# Keg_Cop_-_RJ45_-_6-Pack_Tallboy.net
KiCad netlist of a schematic drawn in EAGLE
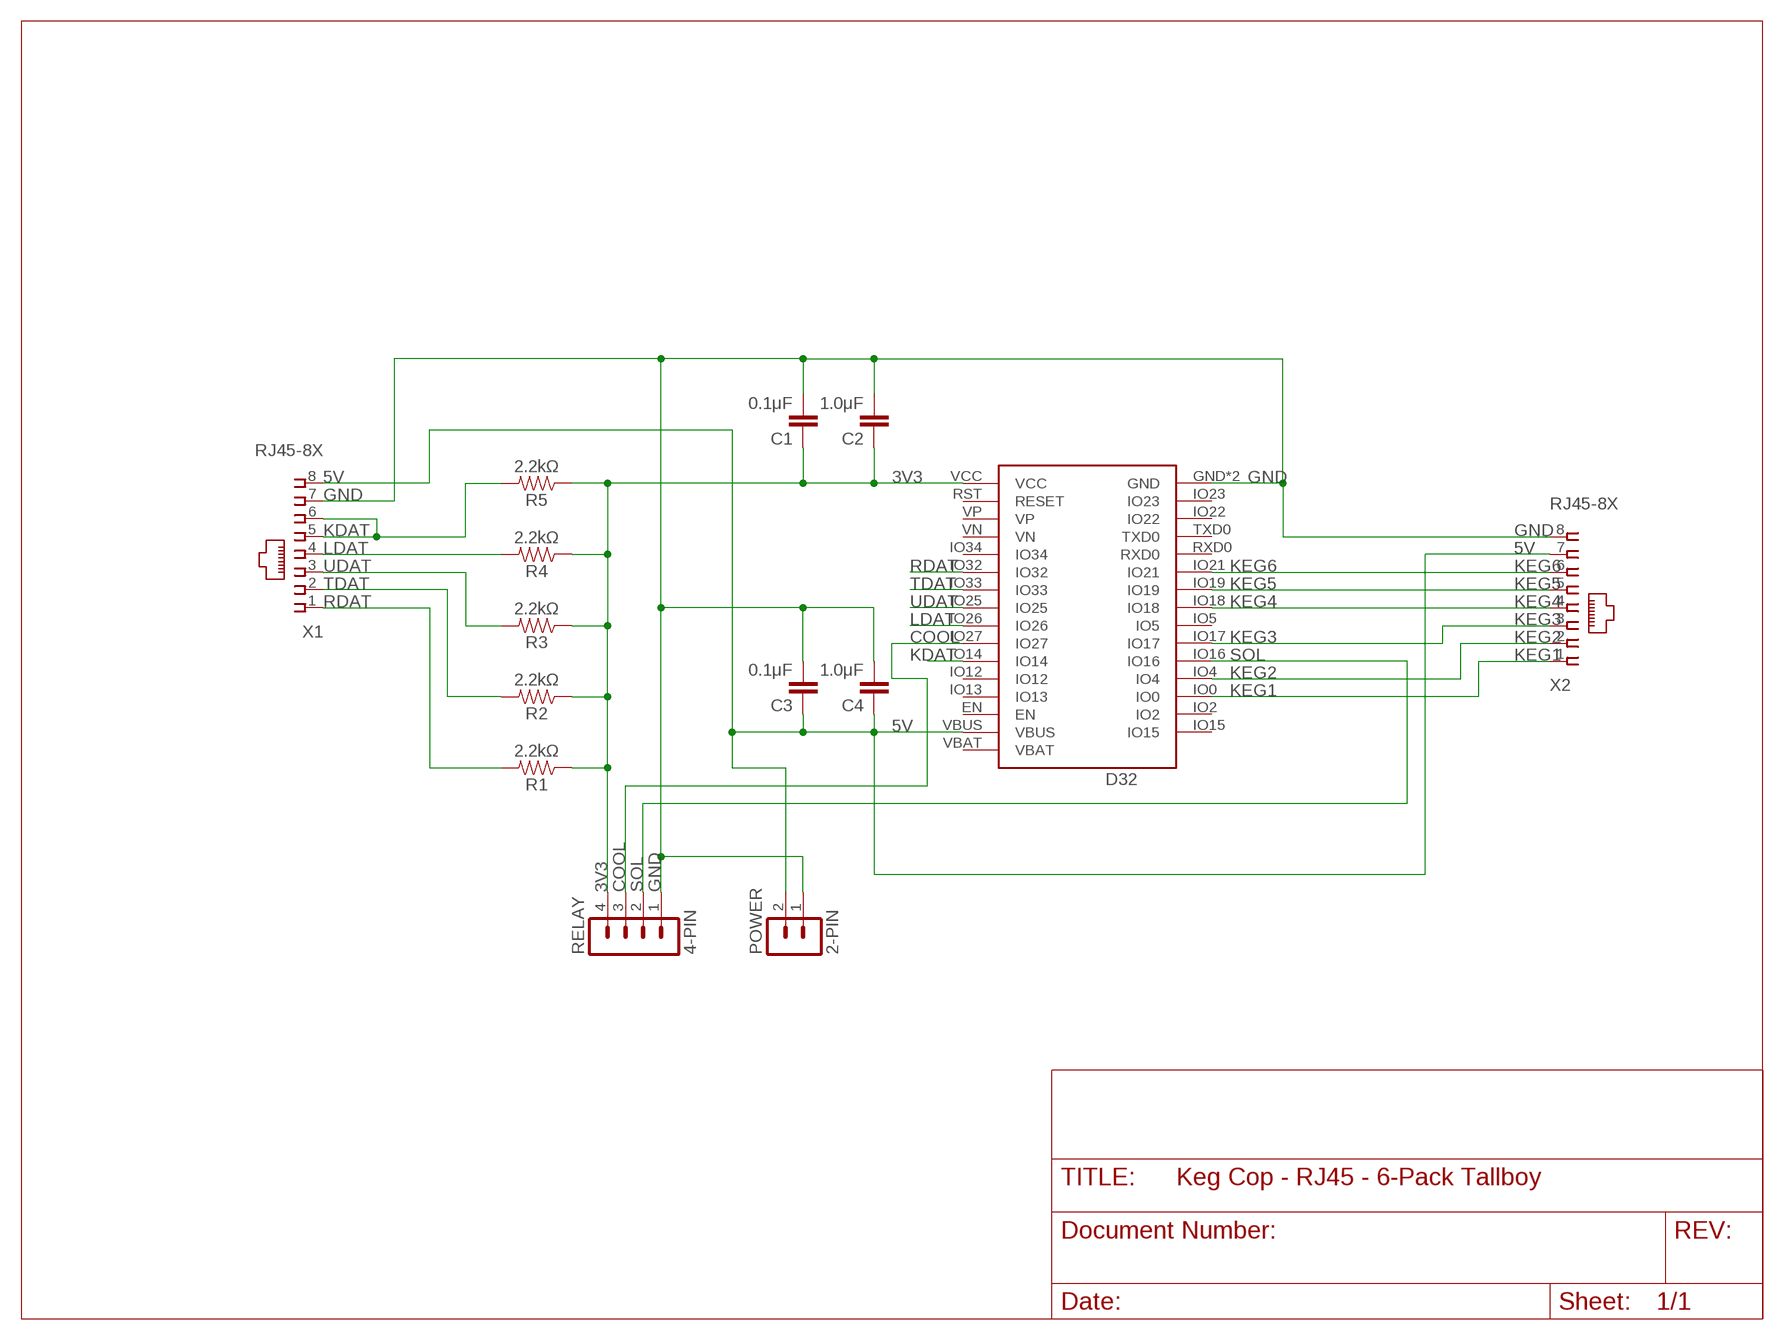
[diagram p0: schematic, sheet 1]

(export (version "E")
  (design (tool "Eeschema 10.0.6"))
  (components
    (comp (ref "C1")
      (value "0.1μF")
      (footprint "eagle-import:CAP_PTH-2.54")
      (libsource (lib "eagle-import") (part "CAP_CERAMIC_2.54"))
    )
    (comp (ref "C2")
      (value "1.0μF")
      (footprint "eagle-import:CAP_PTH-2.54")
      (libsource (lib "eagle-import") (part "CAP_CERAMIC_2.54"))
    )
    (comp (ref "C3")
      (value "0.1μF")
      (footprint "eagle-import:CAP_PTH-2.54")
      (libsource (lib "eagle-import") (part "CAP_CERAMIC_2.54"))
    )
    (comp (ref "C4")
      (value "1.0μF")
      (footprint "eagle-import:CAP_PTH-2.54")
      (libsource (lib "eagle-import") (part "CAP_CERAMIC_2.54"))
    )
    (comp (ref "D32")
      (value "Lolin D32")
      (footprint "eagle-import:D32_NO_BATT")
      (libsource (lib "eagle-import") (part "WEMOS-D32D32_NO_BATT"))
    )
    (comp (ref "POWER")
      (value "2-PIN")
      (footprint "eagle-import:HDR-2_VERT")
      (libsource (lib "eagle-import") (part "HDR-2"))
    )
    (comp (ref "R1")
      (value "2.2kΩ")
      (footprint "eagle-import:AXIAL-0.3")
      (libsource (lib "eagle-import") (part "RESISTORAXIAL-0.3"))
    )
    (comp (ref "R2")
      (value "2.2kΩ")
      (footprint "eagle-import:AXIAL-0.3")
      (libsource (lib "eagle-import") (part "RESISTORAXIAL-0.3"))
    )
    (comp (ref "R3")
      (value "2.2kΩ")
      (footprint "eagle-import:AXIAL-0.3")
      (libsource (lib "eagle-import") (part "RESISTORAXIAL-0.3"))
    )
    (comp (ref "R4")
      (value "2.2kΩ")
      (footprint "eagle-import:AXIAL-0.3")
      (libsource (lib "eagle-import") (part "RESISTORAXIAL-0.3"))
    )
    (comp (ref "R5")
      (value "2.2kΩ")
      (footprint "eagle-import:AXIAL-0.3")
      (libsource (lib "eagle-import") (part "RESISTORAXIAL-0.3"))
    )
    (comp (ref "RELAY")
      (value "4-PIN")
      (footprint "eagle-import:MA04-1")
      (libsource (lib "eagle-import") (part "MA04-1"))
    )
    (comp (ref "X1")
      (value "RJ45-8X")
      (footprint "eagle-import:RJ45-NO-SHIELD")
      (libsource (lib "eagle-import") (part "RJ45-8X"))
    )
    (comp (ref "X2")
      (value "RJ45-8X")
      (footprint "eagle-import:RJ45-NO-SHIELD")
      (libsource (lib "eagle-import") (part "RJ45-8X"))
    )
  )
  (nets
    (net (code "1") (name "/3V3") (class "Default")
      (node (ref "C1") (pin "1") (pinfunction "1_1") (pintype "passive"))
      (node (ref "C2") (pin "1") (pinfunction "1_1") (pintype "passive"))
      (node (ref "D32") (pin "VCC") (pinfunction "VCC_VCC") (pintype "power_in"))
      (node (ref "R1") (pin "P$1") (pinfunction "1_P$1") (pintype "passive"))
      (node (ref "R2") (pin "P$1") (pinfunction "1_P$1") (pintype "passive"))
      (node (ref "R3") (pin "P$1") (pinfunction "1_P$1") (pintype "passive"))
      (node (ref "R4") (pin "P$1") (pinfunction "1_P$1") (pintype "passive"))
      (node (ref "R5") (pin "P$1") (pinfunction "1_P$1") (pintype "passive"))
      (node (ref "RELAY") (pin "4") (pinfunction "4_4") (pintype "passive"))
    )
    (net (code "2") (name "/5V") (class "Default")
      (node (ref "C3") (pin "1") (pinfunction "1_1") (pintype "passive"))
      (node (ref "C4") (pin "1") (pinfunction "1_1") (pintype "passive"))
      (node (ref "D32") (pin "VBUS") (pinfunction "VBUS_VBUS") (pintype "bidirectional"))
      (node (ref "POWER") (pin "2") (pinfunction "2_2") (pintype "passive"))
      (node (ref "X1") (pin "8") (pinfunction "8_8") (pintype "passive"))
      (node (ref "X2") (pin "7") (pinfunction "7_7") (pintype "passive"))
    )
    (net (code "3") (name "/COOL") (class "Default")
      (node (ref "D32") (pin "IO27") (pinfunction "IO27_IO27") (pintype "bidirectional"))
      (node (ref "RELAY") (pin "3") (pinfunction "3_3") (pintype "passive"))
    )
    (net (code "4") (name "/GND") (class "Default")
      (node (ref "C1") (pin "2") (pinfunction "2_2") (pintype "passive"))
      (node (ref "C2") (pin "2") (pinfunction "2_2") (pintype "passive"))
      (node (ref "C3") (pin "2") (pinfunction "2_2") (pintype "passive"))
      (node (ref "C4") (pin "2") (pinfunction "2_2") (pintype "passive"))
      (node (ref "D32") (pin "GND") (pinfunction "GND_GND") (pintype "power_in"))
      (node (ref "D32") (pin "GND2") (pinfunction "GND_GND2") (pintype "power_in"))
      (node (ref "POWER") (pin "1") (pinfunction "1_1") (pintype "passive"))
      (node (ref "RELAY") (pin "1") (pinfunction "1_1") (pintype "passive"))
      (node (ref "X1") (pin "7") (pinfunction "7_7") (pintype "passive"))
      (node (ref "X2") (pin "8") (pinfunction "8_8") (pintype "passive"))
    )
    (net (code "5") (name "/KDAT") (class "Default")
      (node (ref "D32") (pin "IO14") (pinfunction "IO14_IO14") (pintype "bidirectional"))
      (node (ref "R5") (pin "P$2") (pinfunction "2_P$2") (pintype "passive"))
      (node (ref "X1") (pin "5") (pinfunction "5_5") (pintype "passive"))
      (node (ref "X1") (pin "6") (pinfunction "6_6") (pintype "passive"))
    )
    (net (code "6") (name "/KEG1") (class "Default")
      (node (ref "D32") (pin "IO0") (pinfunction "IO0_IO0") (pintype "bidirectional"))
      (node (ref "X2") (pin "1") (pinfunction "1_1") (pintype "passive"))
    )
    (net (code "7") (name "/KEG2") (class "Default")
      (node (ref "D32") (pin "IO4") (pinfunction "IO4_IO4") (pintype "bidirectional"))
      (node (ref "X2") (pin "2") (pinfunction "2_2") (pintype "passive"))
    )
    (net (code "8") (name "/KEG3") (class "Default")
      (node (ref "D32") (pin "IO17") (pinfunction "IO17_IO17") (pintype "bidirectional"))
      (node (ref "X2") (pin "3") (pinfunction "3_3") (pintype "passive"))
    )
    (net (code "9") (name "/KEG4") (class "Default")
      (node (ref "D32") (pin "IO18") (pinfunction "IO18_IO18") (pintype "bidirectional"))
      (node (ref "X2") (pin "4") (pinfunction "4_4") (pintype "passive"))
    )
    (net (code "10") (name "/KEG5") (class "Default")
      (node (ref "D32") (pin "IO19") (pinfunction "IO19_IO19") (pintype "bidirectional"))
      (node (ref "X2") (pin "5") (pinfunction "5_5") (pintype "passive"))
    )
    (net (code "11") (name "/KEG6") (class "Default")
      (node (ref "D32") (pin "IO21") (pinfunction "IO21_IO21") (pintype "bidirectional"))
      (node (ref "X2") (pin "6") (pinfunction "6_6") (pintype "passive"))
    )
    (net (code "12") (name "/LDAT") (class "Default")
      (node (ref "D32") (pin "IO26") (pinfunction "IO26_IO26") (pintype "bidirectional"))
      (node (ref "R4") (pin "P$2") (pinfunction "2_P$2") (pintype "passive"))
      (node (ref "X1") (pin "4") (pinfunction "4_4") (pintype "passive"))
    )
    (net (code "13") (name "/RDAT") (class "Default")
      (node (ref "D32") (pin "IO32") (pinfunction "IO32_IO32") (pintype "bidirectional"))
      (node (ref "R1") (pin "P$2") (pinfunction "2_P$2") (pintype "passive"))
      (node (ref "X1") (pin "1") (pinfunction "1_1") (pintype "passive"))
    )
    (net (code "14") (name "/SOL") (class "Default")
      (node (ref "D32") (pin "IO16") (pinfunction "IO16_IO16") (pintype "bidirectional"))
      (node (ref "RELAY") (pin "2") (pinfunction "2_2") (pintype "passive"))
    )
    (net (code "15") (name "/TDAT") (class "Default")
      (node (ref "D32") (pin "IO33") (pinfunction "IO33_IO33") (pintype "bidirectional"))
      (node (ref "R2") (pin "P$2") (pinfunction "2_P$2") (pintype "passive"))
      (node (ref "X1") (pin "2") (pinfunction "2_2") (pintype "passive"))
    )
    (net (code "16") (name "/UDAT") (class "Default")
      (node (ref "D32") (pin "IO25") (pinfunction "IO25_IO25") (pintype "bidirectional"))
      (node (ref "R3") (pin "P$2") (pinfunction "2_P$2") (pintype "passive"))
      (node (ref "X1") (pin "3") (pinfunction "3_3") (pintype "passive"))
    )
    (net (code "17") (name "unconnected-(D32-PadEN)") (class "Default")
      (node (ref "D32") (pin "EN") (pinfunction "EN_EN") (pintype "bidirectional"))
    )
    (net (code "18") (name "unconnected-(D32-PadIO2)") (class "Default")
      (node (ref "D32") (pin "IO2") (pinfunction "IO2_IO2") (pintype "bidirectional"))
    )
    (net (code "19") (name "unconnected-(D32-PadIO5)") (class "Default")
      (node (ref "D32") (pin "IO5") (pinfunction "IO5_IO5") (pintype "bidirectional"))
    )
    (net (code "20") (name "unconnected-(D32-PadIO12)") (class "Default")
      (node (ref "D32") (pin "IO12") (pinfunction "IO12_IO12") (pintype "bidirectional"))
    )
    (net (code "21") (name "unconnected-(D32-PadIO13)") (class "Default")
      (node (ref "D32") (pin "IO13") (pinfunction "IO13_IO13") (pintype "bidirectional"))
    )
    (net (code "22") (name "unconnected-(D32-PadIO15)") (class "Default")
      (node (ref "D32") (pin "IO15") (pinfunction "IO15_IO15") (pintype "bidirectional"))
    )
    (net (code "23") (name "unconnected-(D32-PadIO22)") (class "Default")
      (node (ref "D32") (pin "IO22") (pinfunction "IO22_IO22") (pintype "bidirectional"))
    )
    (net (code "24") (name "unconnected-(D32-PadIO23)") (class "Default")
      (node (ref "D32") (pin "IO23") (pinfunction "IO23_IO23") (pintype "bidirectional"))
    )
    (net (code "25") (name "unconnected-(D32-PadIO34)") (class "Default")
      (node (ref "D32") (pin "IO34") (pinfunction "IO34_IO34") (pintype "bidirectional"))
    )
    (net (code "26") (name "unconnected-(D32-PadRXD0)") (class "Default")
      (node (ref "D32") (pin "RXD0") (pinfunction "RXD0_RXD0") (pintype "input"))
    )
    (net (code "27") (name "unconnected-(D32-PadTXD0)") (class "Default")
      (node (ref "D32") (pin "TXD0") (pinfunction "TXD0_TXD0") (pintype "output"))
    )
    (net (code "28") (name "unconnected-(D32-PadVBAT)") (class "Default")
      (node (ref "D32") (pin "VBAT") (pinfunction "VBAT_VBAT") (pintype "bidirectional"))
    )
    (net (code "29") (name "unconnected-(D32-PadVN)") (class "Default")
      (node (ref "D32") (pin "VN") (pinfunction "VN_VN") (pintype "bidirectional"))
    )
    (net (code "30") (name "unconnected-(D32-PadVP)") (class "Default")
      (node (ref "D32") (pin "VP") (pinfunction "VP_VP") (pintype "bidirectional"))
    )
    (net (code "31") (name "unconnected-(D32-RESET-PadRST)") (class "Default")
      (node (ref "D32") (pin "RST") (pinfunction "RESET_RST") (pintype "bidirectional"))
    )
  )
)
